# Stlink-v4-dongle.net
KiCad netlist of a schematic drawn in Altium Designer
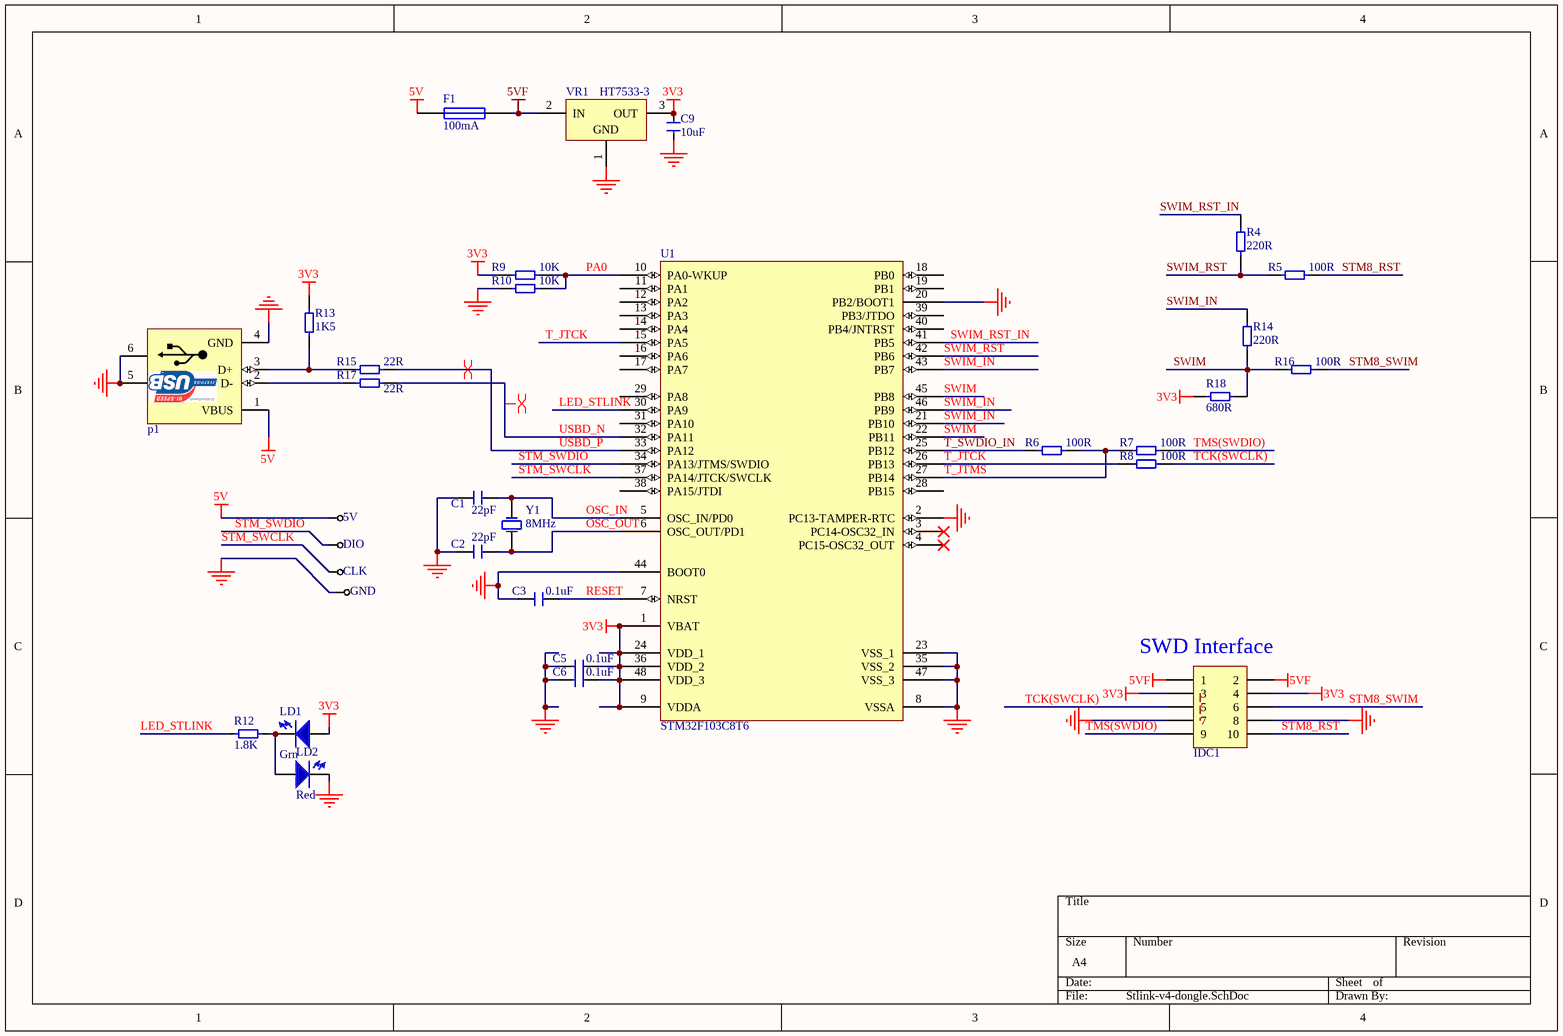
[diagram p0: Stlink-v4-dongle.SchDoc]

(export (version "E")
  (design (tool "Eeschema 10.0.6"))
  (components
    (comp (ref "5V")
      (value "Test Point")
      (footprint "TEST POINT SMALL")
      (libsource (lib "My Library") (part "Test Point"))
    )
    (comp (ref "C1")
      (value "22pF")
      (footprint "CAP0603")
      (fields (field (name "Comment") "Capacitor SMD"))
      (libsource (lib "Rahimi librery") (part "Capacitor SMD"))
    )
    (comp (ref "C2")
      (value "22pF")
      (footprint "CAP0603")
      (fields (field (name "Comment") "Capacitor SMD"))
      (libsource (lib "Rahimi librery") (part "Capacitor SMD"))
    )
    (comp (ref "C3")
      (value "0.1uF")
      (footprint "CAP0603")
      (fields (field (name "Comment") "Capacitor SMD"))
      (libsource (lib "Rahimi librery") (part "Capacitor SMD"))
    )
    (comp (ref "C5")
      (value "0.1uF")
      (footprint "CAP0603")
      (fields (field (name "Comment") "Capacitor SMD"))
      (libsource (lib "Rahimi librery") (part "Capacitor SMD"))
    )
    (comp (ref "C6")
      (value "0.1uF")
      (footprint "CAP0603")
      (fields (field (name "Comment") "Capacitor SMD"))
      (libsource (lib "Rahimi librery") (part "Capacitor SMD"))
    )
    (comp (ref "C9")
      (value "10uF")
      (footprint "0805 Capacitor")
      (fields (field (name "Comment") "Capacitor SMD"))
      (libsource (lib "") (part "Capacitor SMD_1"))
    )
    (comp (ref "CLK")
      (value "Test Point")
      (footprint "TEST POINT SMALL")
      (libsource (lib "My Library") (part "Test Point"))
    )
    (comp (ref "DIO")
      (value "Test Point")
      (footprint "TEST POINT SMALL")
      (libsource (lib "My Library") (part "Test Point"))
    )
    (comp (ref "F1")
      (value "100mA")
      (footprint "RES0805")
      (description "100mA resetable fuse")
      (fields (field (name "PUBLISHER") "Altium Limited"))
      (libsource (lib "Miscellaneous Devices") (part "Fuse 1"))
    )
    (comp (ref "GND")
      (value "Test Point")
      (footprint "TEST POINT SMALL")
      (libsource (lib "My Library") (part "Test Point"))
    )
    (comp (ref "IDC1")
      (value "CONNECTOR_IDC_5X2")
      (footprint "IDC2.54-10PIN - CROSS")
      (description "Header, 5-Pin, Dual row")
      (fields
        (field (name "MANUFACTURER") "CHINA")
        (field (name "PUBLISHER") "ABBAS BASEREH")
        (field (name "DESIGNER") "ABBAS BASEREH")
      )
      (libsource (lib "Mofidi3D") (part "IDC_5X2 HEADER"))
    )
    (comp (ref "LD1")
      (value "Grn")
      (footprint "LED_0805")
      (libsource (lib "Rahimi librery") (part "LED SMD"))
    )
    (comp (ref "LD2")
      (value "Red")
      (footprint "LED_0805")
      (libsource (lib "Rahimi librery") (part "LED SMD"))
    )
    (comp (ref "p1")
      (value "USB Connector")
      (footprint "USB A TYPE Right Angle")
      (description "USB Connector-A Type")
      (fields (field (name "DESIGNER") "ABBAS BASEREH") (field (name "PUBLISHER") "ABBAS BASEREH"))
      (libsource (lib "Mofidi3D") (part "USB A CONNECTOR"))
    )
    (comp (ref "R4")
      (value "220R")
      (footprint "RES0603")
      (fields (field (name "Comment") "Resistor SMD"))
      (libsource (lib "Rahimi librery") (part "Resistor SMD"))
    )
    (comp (ref "R5")
      (value "100R")
      (footprint "RES0603")
      (fields (field (name "Comment") "Resistor SMD"))
      (libsource (lib "Rahimi librery") (part "Resistor SMD"))
    )
    (comp (ref "R6")
      (value "100R")
      (footprint "RES0603")
      (fields (field (name "Comment") "Resistor SMD"))
      (libsource (lib "Rahimi librery") (part "Resistor SMD"))
    )
    (comp (ref "R7")
      (value "100R")
      (footprint "RES0603")
      (fields (field (name "Comment") "Resistor SMD"))
      (libsource (lib "Rahimi librery") (part "Resistor SMD"))
    )
    (comp (ref "R8")
      (value "100R")
      (footprint "RES0603")
      (fields (field (name "Comment") "Resistor SMD"))
      (libsource (lib "Rahimi librery") (part "Resistor SMD"))
    )
    (comp (ref "R9")
      (value "Resistor SMD")
      (footprint "RES0603")
      (fields (field (name "ALTIUM_UNNAMED_1") "10K"))
      (libsource (lib "Rahimi librery") (part "Resistor SMD"))
    )
    (comp (ref "R10")
      (value "Resistor SMD")
      (footprint "RES0603")
      (fields (field (name "ALTIUM_UNNAMED_1") "10K"))
      (libsource (lib "Rahimi librery") (part "Resistor SMD"))
    )
    (comp (ref "R12")
      (value "1.8K")
      (footprint "RES0603")
      (fields (field (name "Comment") "Resistor SMD"))
      (libsource (lib "") (part "Resistor SMD_1"))
    )
    (comp (ref "R13")
      (value "1K5")
      (footprint "RES0603")
      (fields (field (name "Comment") "Resistor SMD"))
      (libsource (lib "Rahimi librery") (part "Resistor SMD"))
    )
    (comp (ref "R14")
      (value "220R")
      (footprint "RES0603")
      (fields (field (name "Comment") "Resistor SMD"))
      (libsource (lib "Rahimi librery") (part "Resistor SMD"))
    )
    (comp (ref "R15")
      (value "22R")
      (footprint "RES0603")
      (fields (field (name "Comment") "Resistor SMD"))
      (libsource (lib "Rahimi librery") (part "Resistor SMD"))
    )
    (comp (ref "R16")
      (value "100R")
      (footprint "RES0603")
      (fields (field (name "Comment") "Resistor SMD"))
      (libsource (lib "Rahimi librery") (part "Resistor SMD"))
    )
    (comp (ref "R17")
      (value "22R")
      (footprint "RES0603")
      (fields (field (name "Comment") "Resistor SMD"))
      (libsource (lib "Rahimi librery") (part "Resistor SMD"))
    )
    (comp (ref "R18")
      (value "680R")
      (footprint "RES0603")
      (fields (field (name "Comment") "Resistor SMD"))
      (libsource (lib "Rahimi librery") (part "Resistor SMD"))
    )
    (comp (ref "U1")
      (value "STM32F103C8T6")
      (footprint "LQFP48")
      (description "STM32 ARM-based 32-bit MCU with 64 Kbytes Flash, 48-pin LQFP, Industrial Temperature")
      (fields (field (name "PUBLISHER") "Altium Limited"))
      (libsource (lib "ST Microcontroller 32-Bit STM32") (part "STM32F103C8T6"))
    )
    (comp (ref "VR1")
      (value "HT7533-3")
      (footprint "SOT89N")
      (description "3.0V 100mA Low Power,  Low Dropout Voltage (LDO) Regulator")
      (fields (field (name "PUBLISHER") "Altium Limited"))
      (libsource (lib "Holtek Power Mgt Voltage Regulator") (part "HT7530-1"))
    )
    (comp (ref "Y1")
      (value "8MHz")
      (footprint "CRYSTAL Small")
      (description "XTAL Crystal")
      (libsource (lib "My Library") (part "XTAL"))
    )
  )
  (nets
    (net (code "1") (name "/LED_STLINK") (class "Default")
      (node (ref "R12") (pin "2") (pintype "passive"))
      (node (ref "U1") (pin "30") (pinfunction "PA9_30") (pintype "bidirectional"))
    )
    (net (code "2") (name "/OSC_IN") (class "Default")
      (node (ref "C1") (pin "2") (pintype "passive"))
      (node (ref "U1") (pin "5") (pinfunction "OSC_IN/PD0_5") (pintype "passive"))
      (node (ref "Y1") (pin "1") (pinfunction "OSC1_1") (pintype "passive"))
    )
    (net (code "3") (name "/OSC_OUT") (class "Default")
      (node (ref "C2") (pin "2") (pintype "passive"))
      (node (ref "U1") (pin "6") (pinfunction "OSC_OUT/PD1_6") (pintype "passive"))
      (node (ref "Y1") (pin "2") (pinfunction "OSC2_2") (pintype "passive"))
    )
    (net (code "4") (name "/PA0") (class "Default")
      (node (ref "R10") (pin "2") (pintype "passive"))
      (node (ref "R9") (pin "2") (pintype "passive"))
      (node (ref "U1") (pin "10") (pinfunction "PA0-WKUP_10") (pintype "bidirectional"))
    )
    (net (code "5") (name "/RESET") (class "Default")
      (node (ref "C3") (pin "2") (pintype "passive"))
      (node (ref "U1") (pin "7") (pinfunction "NRST_7") (pintype "bidirectional"))
    )
    (net (code "6") (name "/STM8_RST") (class "Default")
      (node (ref "IDC1") (pin "10") (pinfunction "10_10") (pintype "passive"))
      (node (ref "R5") (pin "2") (pintype "passive"))
    )
    (net (code "7") (name "/STM8_SWIM") (class "Default")
      (node (ref "IDC1") (pin "6") (pinfunction "6_6") (pintype "passive"))
      (node (ref "R16") (pin "2") (pintype "passive"))
    )
    (net (code "8") (name "/STM_SWCLK") (class "Default")
      (node (ref "CLK") (pin "1") (pinfunction "T_1") (pintype "passive"))
      (node (ref "U1") (pin "37") (pinfunction "PA14/JTCK/SWCLK_37") (pintype "bidirectional"))
    )
    (net (code "9") (name "/STM_SWDIO") (class "Default")
      (node (ref "DIO") (pin "1") (pinfunction "T_1") (pintype "passive"))
      (node (ref "U1") (pin "34") (pinfunction "PA13/JTMS/SWDIO_34") (pintype "bidirectional"))
    )
    (net (code "10") (name "/SWIM") (class "Default")
      (node (ref "R14") (pin "1") (pintype "passive"))
      (node (ref "R16") (pin "1") (pintype "passive"))
      (node (ref "R18") (pin "1") (pintype "passive"))
      (node (ref "U1") (pin "22") (pinfunction "PB11_22") (pintype "bidirectional"))
      (node (ref "U1") (pin "45") (pinfunction "PB8_45") (pintype "bidirectional"))
    )
    (net (code "11") (name "/SWIM_IN") (class "Default")
      (node (ref "R14") (pin "2") (pintype "passive"))
      (node (ref "U1") (pin "21") (pinfunction "PB10_21") (pintype "bidirectional"))
      (node (ref "U1") (pin "43") (pinfunction "PB7_43") (pintype "bidirectional"))
      (node (ref "U1") (pin "46") (pinfunction "PB9_46") (pintype "bidirectional"))
    )
    (net (code "12") (name "/SWIM_RST") (class "Default")
      (node (ref "R4") (pin "1") (pintype "passive"))
      (node (ref "R5") (pin "1") (pintype "passive"))
      (node (ref "U1") (pin "42") (pinfunction "PB6_42") (pintype "bidirectional"))
    )
    (net (code "13") (name "/SWIM_RST_IN") (class "Default")
      (node (ref "R4") (pin "2") (pintype "passive"))
      (node (ref "U1") (pin "41") (pinfunction "PB5_41") (pintype "bidirectional"))
    )
    (net (code "14") (name "/TCK(SWCLK)") (class "Default")
      (node (ref "IDC1") (pin "5") (pinfunction "5_5") (pintype "passive"))
      (node (ref "R8") (pin "2") (pintype "passive"))
    )
    (net (code "15") (name "/TMS(SWDIO)") (class "Default")
      (node (ref "IDC1") (pin "9") (pinfunction "9_9") (pintype "passive"))
      (node (ref "R7") (pin "2") (pintype "passive"))
    )
    (net (code "16") (name "/T_JTCK") (class "Default")
      (node (ref "R8") (pin "1") (pintype "passive"))
      (node (ref "U1") (pin "15") (pinfunction "PA5_15") (pintype "bidirectional"))
      (node (ref "U1") (pin "26") (pinfunction "PB13_26") (pintype "bidirectional"))
    )
    (net (code "17") (name "/T_JTMS") (class "Default")
      (node (ref "R6") (pin "2") (pintype "passive"))
      (node (ref "R7") (pin "1") (pintype "passive"))
      (node (ref "U1") (pin "27") (pinfunction "PB14_27") (pintype "bidirectional"))
    )
    (net (code "18") (name "/T_SWDIO_IN") (class "Default")
      (node (ref "R6") (pin "1") (pintype "passive"))
      (node (ref "U1") (pin "25") (pinfunction "PB12_25") (pintype "bidirectional"))
    )
    (net (code "19") (name "/USBD_N") (class "Default")
      (node (ref "R17") (pin "2") (pintype "passive"))
      (node (ref "U1") (pin "32") (pinfunction "PA11_32") (pintype "bidirectional"))
    )
    (net (code "20") (name "/USBD_P") (class "Default")
      (node (ref "R15") (pin "2") (pintype "passive"))
      (node (ref "U1") (pin "33") (pinfunction "PA12_33") (pintype "bidirectional"))
    )
    (net (code "21") (name "3V3") (class "Default")
      (node (ref "C5") (pin "2") (pintype "passive"))
      (node (ref "C6") (pin "2") (pintype "passive"))
      (node (ref "C9") (pin "2") (pintype "passive"))
      (node (ref "IDC1") (pin "3") (pinfunction "3_3") (pintype "passive"))
      (node (ref "IDC1") (pin "4") (pinfunction "4_4") (pintype "passive"))
      (node (ref "LD1") (pin "1") (pinfunction "A_1") (pintype "passive"))
      (node (ref "R13") (pin "2") (pintype "passive"))
      (node (ref "R18") (pin "2") (pintype "passive"))
      (node (ref "R9") (pin "1") (pintype "passive"))
      (node (ref "U1") (pin "1") (pinfunction "VBAT_1") (pintype "power_in"))
      (node (ref "U1") (pin "24") (pinfunction "VDD_1_24") (pintype "power_in"))
      (node (ref "U1") (pin "36") (pinfunction "VDD_2_36") (pintype "power_in"))
      (node (ref "U1") (pin "48") (pinfunction "VDD_3_48") (pintype "power_in"))
      (node (ref "U1") (pin "9") (pinfunction "VDDA_9") (pintype "power_in"))
      (node (ref "VR1") (pin "3") (pinfunction "OUT_3") (pintype "power_in"))
    )
    (net (code "22") (name "5V") (class "Default")
      (node (ref "5V") (pin "1") (pinfunction "T_1") (pintype "passive"))
      (node (ref "F1") (pin "1") (pinfunction "1_1") (pintype "passive"))
      (node (ref "p1") (pin "1") (pinfunction "VBUS_1") (pintype "power_in"))
    )
    (net (code "23") (name "5VF") (class "Default")
      (node (ref "F1") (pin "2") (pinfunction "2_2") (pintype "passive"))
      (node (ref "IDC1") (pin "1") (pinfunction "1_1") (pintype "passive"))
      (node (ref "IDC1") (pin "2") (pinfunction "2_2") (pintype "passive"))
      (node (ref "VR1") (pin "2") (pinfunction "IN_2") (pintype "power_in"))
    )
    (net (code "24") (name "GND") (class "Default")
      (node (ref "C1") (pin "1") (pintype "passive"))
      (node (ref "C2") (pin "1") (pintype "passive"))
      (node (ref "C3") (pin "1") (pintype "passive"))
      (node (ref "C5") (pin "1") (pintype "passive"))
      (node (ref "C6") (pin "1") (pintype "passive"))
      (node (ref "C9") (pin "1") (pintype "passive"))
      (node (ref "GND") (pin "1") (pinfunction "T_1") (pintype "passive"))
      (node (ref "IDC1") (pin "7") (pinfunction "7_7") (pintype "passive"))
      (node (ref "IDC1") (pin "8") (pinfunction "8_8") (pintype "passive"))
      (node (ref "LD2") (pin "2") (pinfunction "K_2") (pintype "passive"))
      (node (ref "R10") (pin "1") (pintype "passive"))
      (node (ref "U1") (pin "2") (pinfunction "PC13-TAMPER-RTC_2") (pintype "bidirectional"))
      (node (ref "U1") (pin "20") (pinfunction "PB2/BOOT1_20") (pintype "passive"))
      (node (ref "U1") (pin "23") (pinfunction "VSS_1_23") (pintype "power_in"))
      (node (ref "U1") (pin "35") (pinfunction "VSS_2_35") (pintype "power_in"))
      (node (ref "U1") (pin "44") (pinfunction "BOOT0_44") (pintype "passive"))
      (node (ref "U1") (pin "47") (pinfunction "VSS_3_47") (pintype "power_in"))
      (node (ref "U1") (pin "8") (pinfunction "VSSA_8") (pintype "power_in"))
      (node (ref "VR1") (pin "1") (pinfunction "GND_1") (pintype "power_in"))
      (node (ref "p1") (pin "4") (pinfunction "GND_4") (pintype "power_in"))
      (node (ref "p1") (pin "5") (pinfunction "MH_5") (pintype "power_in"))
      (node (ref "p1") (pin "6") (pinfunction "MH_6") (pintype "power_in"))
    )
    (net (code "25") (name "Net-(LD1-K)") (class "Default")
      (node (ref "LD1") (pin "2") (pinfunction "K_2") (pintype "passive"))
      (node (ref "LD2") (pin "1") (pinfunction "A_1") (pintype "passive"))
      (node (ref "R12") (pin "1") (pintype "passive"))
    )
    (net (code "26") (name "Net-(p1-D+)") (class "Default")
      (node (ref "R13") (pin "1") (pintype "passive"))
      (node (ref "R15") (pin "1") (pintype "passive"))
      (node (ref "p1") (pin "3") (pinfunction "D+_3") (pintype "bidirectional"))
    )
    (net (code "27") (name "Net-(p1-D-)") (class "Default")
      (node (ref "R17") (pin "1") (pintype "passive"))
      (node (ref "p1") (pin "2") (pinfunction "D-_2") (pintype "bidirectional"))
    )
    (net (code "28") (name "unconnected-(U1-PA1-Pad11)") (class "Default")
      (node (ref "U1") (pin "11") (pinfunction "PA1_11") (pintype "bidirectional"))
    )
    (net (code "29") (name "unconnected-(U1-PA2-Pad12)") (class "Default")
      (node (ref "U1") (pin "12") (pinfunction "PA2_12") (pintype "bidirectional"))
    )
    (net (code "30") (name "unconnected-(U1-PA3-Pad13)") (class "Default")
      (node (ref "U1") (pin "13") (pinfunction "PA3_13") (pintype "bidirectional"))
    )
    (net (code "31") (name "unconnected-(U1-PA4-Pad14)") (class "Default")
      (node (ref "U1") (pin "14") (pinfunction "PA4_14") (pintype "bidirectional"))
    )
    (net (code "32") (name "unconnected-(U1-PA6-Pad16)") (class "Default")
      (node (ref "U1") (pin "16") (pinfunction "PA6_16") (pintype "bidirectional"))
    )
    (net (code "33") (name "unconnected-(U1-PA7-Pad17)") (class "Default")
      (node (ref "U1") (pin "17") (pinfunction "PA7_17") (pintype "bidirectional"))
    )
    (net (code "34") (name "unconnected-(U1-PA8-Pad29)") (class "Default")
      (node (ref "U1") (pin "29") (pinfunction "PA8_29") (pintype "bidirectional"))
    )
    (net (code "35") (name "unconnected-(U1-PA10-Pad31)") (class "Default")
      (node (ref "U1") (pin "31") (pinfunction "PA10_31") (pintype "bidirectional"))
    )
    (net (code "36") (name "unconnected-(U1-PA15{slash}JTDI-Pad38)") (class "Default")
      (node (ref "U1") (pin "38") (pinfunction "PA15/JTDI_38") (pintype "bidirectional"))
    )
    (net (code "37") (name "unconnected-(U1-PB0-Pad18)") (class "Default")
      (node (ref "U1") (pin "18") (pinfunction "PB0_18") (pintype "bidirectional"))
    )
    (net (code "38") (name "unconnected-(U1-PB1-Pad19)") (class "Default")
      (node (ref "U1") (pin "19") (pinfunction "PB1_19") (pintype "bidirectional"))
    )
    (net (code "39") (name "unconnected-(U1-PB3{slash}JTDO-Pad39)") (class "Default")
      (node (ref "U1") (pin "39") (pinfunction "PB3/JTDO_39") (pintype "bidirectional"))
    )
    (net (code "40") (name "unconnected-(U1-PB4{slash}JNTRST-Pad40)") (class "Default")
      (node (ref "U1") (pin "40") (pinfunction "PB4/JNTRST_40") (pintype "bidirectional"))
    )
    (net (code "41") (name "unconnected-(U1-PB15-Pad28)") (class "Default")
      (node (ref "U1") (pin "28") (pinfunction "PB15_28") (pintype "bidirectional"))
    )
    (net (code "42") (name "unconnected-(U1-PC14-OSC32_IN-Pad3)") (class "Default")
      (node (ref "U1") (pin "3") (pinfunction "PC14-OSC32_IN_3") (pintype "bidirectional+no_connect"))
    )
    (net (code "43") (name "unconnected-(U1-PC15-OSC32_OUT-Pad4)") (class "Default")
      (node (ref "U1") (pin "4") (pinfunction "PC15-OSC32_OUT_4") (pintype "bidirectional+no_connect"))
    )
  )
)
